# brick_i2c_ktemp.net
KiCad netlist of a schematic drawn in EAGLE
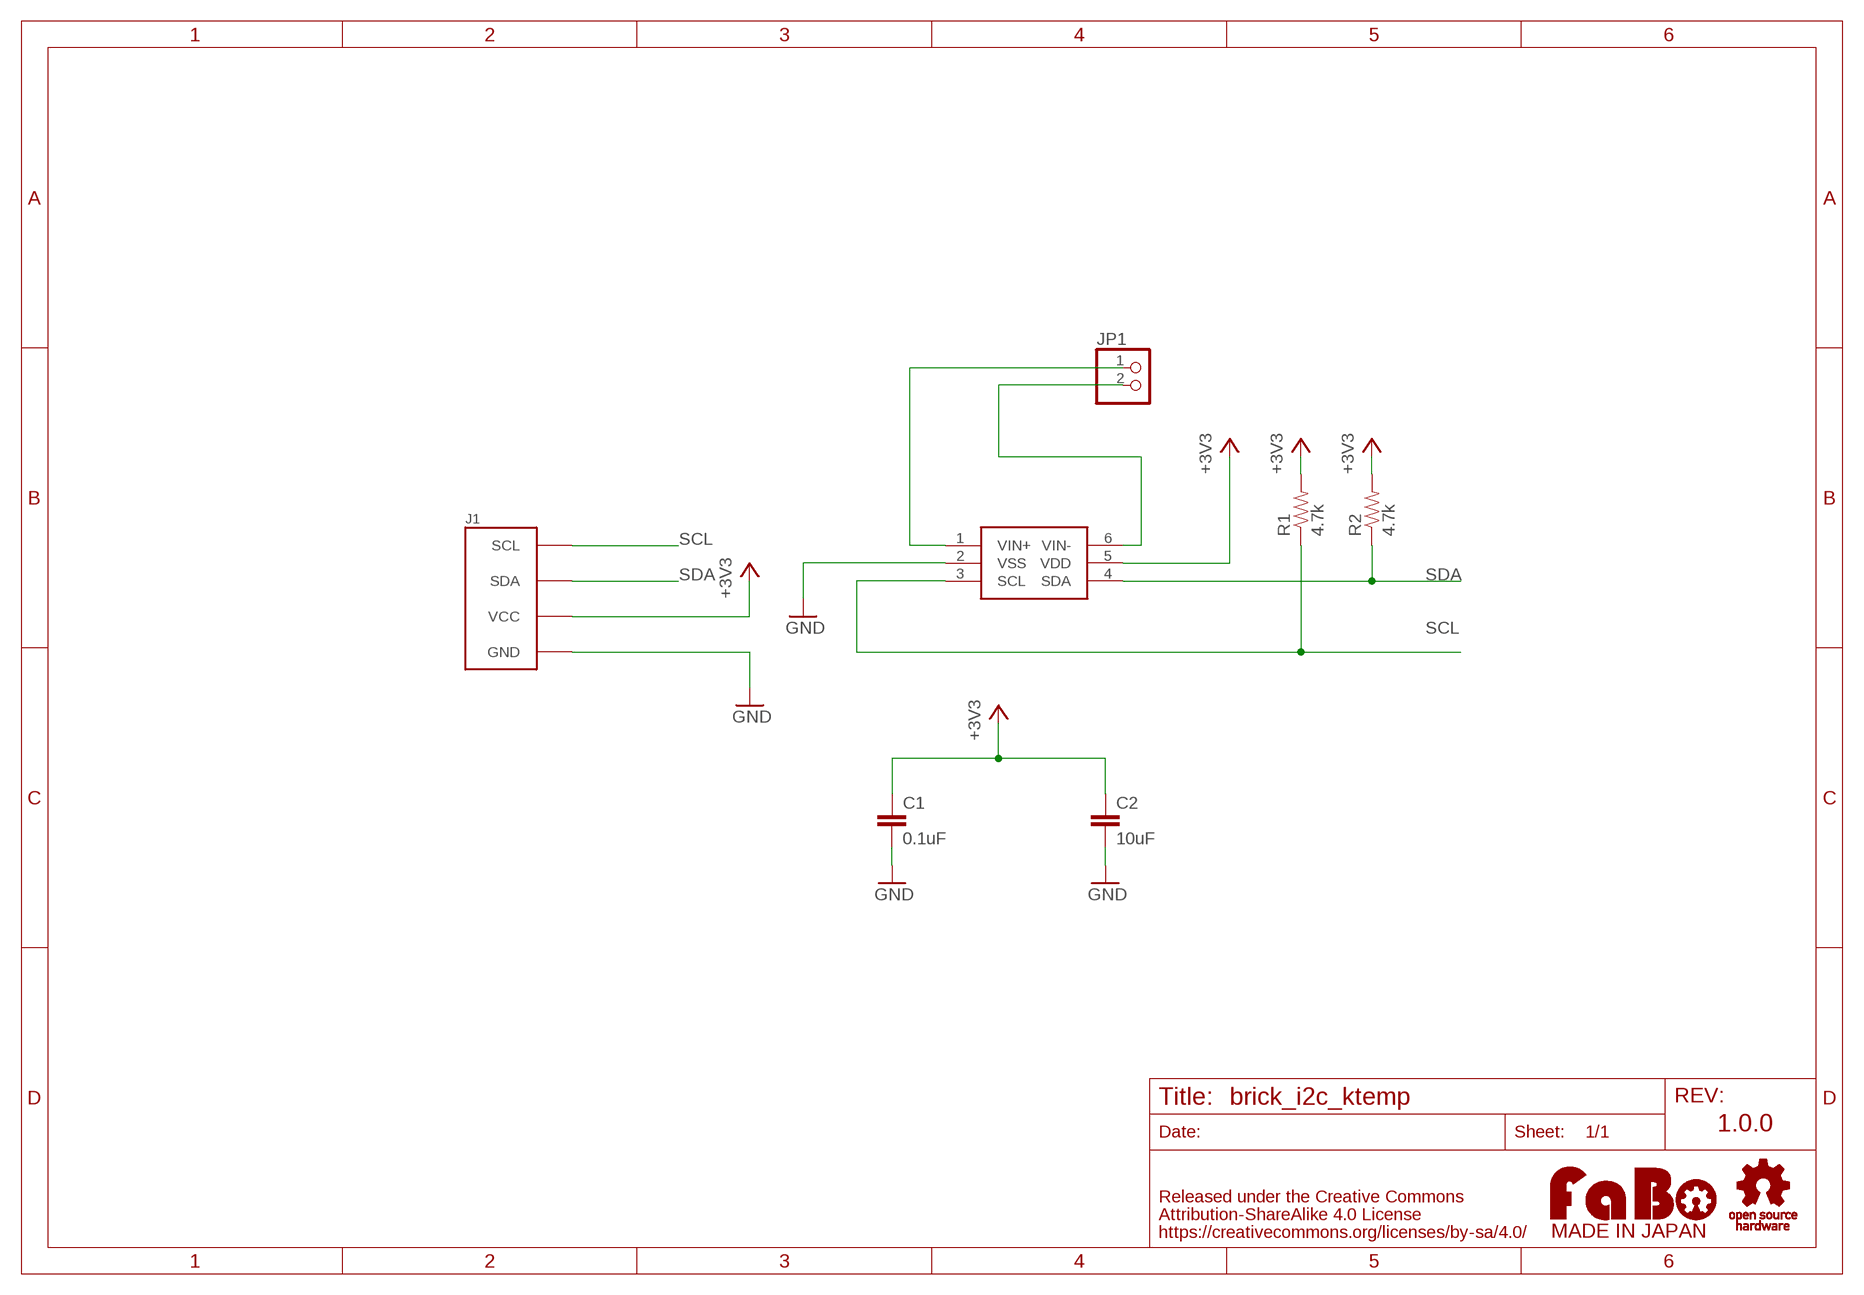
[diagram p0: schematic, sheet 1]

(export (version "E")
  (design (tool "Eeschema 10.0.6"))
  (components
    (comp (ref "C1")
      (value "0.1uF")
      (footprint "eagle-import:EIA0603")
      (libsource (lib "eagle-import") (part "CAP-EIA0603"))
    )
    (comp (ref "C2")
      (value "10uF")
      (footprint "eagle-import:EIA0603")
      (libsource (lib "eagle-import") (part "CAP-EIA0603"))
    )
    (comp (ref "J1")
      (value "BRICK_I2C")
      (footprint "eagle-import:BRICK_I2C")
      (libsource (lib "eagle-import") (part "BRICK_I2C"))
    )
    (comp (ref "JP1")
      (value "PINHD-1X2")
      (footprint "eagle-import:1X02")
      (libsource (lib "eagle-import") (part "PINHD-1X2"))
    )
    (comp (ref "R1")
      (value "4.7k")
      (footprint "eagle-import:EIA0603")
      (libsource (lib "eagle-import") (part "RES-EIA0603"))
    )
    (comp (ref "R2")
      (value "4.7k")
      (footprint "eagle-import:EIA0603")
      (libsource (lib "eagle-import") (part "RES-EIA0603"))
    )
    (comp (ref "U$2")
      (value "MICROCHIP-MCP3421")
      (footprint "eagle-import:MICROCHIP-MCP3421")
      (libsource (lib "eagle-import") (part "MICROCHIP-MCP3421"))
    )
    (comp (ref "U$3")
      (value "LOGO_OSHW_T-M")
      (footprint "eagle-import:LOGO_OSHW_T_M")
      (libsource (lib "eagle-import") (part "LOGO_OSHW_T-M"))
    )
    (comp (ref "U$4")
      (value "LOGO_FABO-M")
      (footprint "eagle-import:LOGO_FABO_M")
      (libsource (lib "eagle-import") (part "LOGO_FABO-M"))
    )
  )
  (nets
    (net (code "1") (name "+3V3") (class "Default")
      (node (ref "C1") (pin "1") (pinfunction "1_1") (pintype "passive"))
      (node (ref "C2") (pin "1") (pinfunction "1_1") (pintype "passive"))
      (node (ref "J1") (pin "VCC") (pinfunction "VCC_VCC") (pintype "bidirectional"))
      (node (ref "R1") (pin "2") (pinfunction "2_2") (pintype "passive"))
      (node (ref "R2") (pin "2") (pinfunction "2_2") (pintype "passive"))
      (node (ref "U$2") (pin "5") (pinfunction "VDD_5") (pintype "bidirectional"))
    )
    (net (code "2") (name "/SCL") (class "Default")
      (node (ref "J1") (pin "SCL") (pinfunction "SCL_SCL") (pintype "bidirectional"))
      (node (ref "R1") (pin "1") (pinfunction "1_1") (pintype "passive"))
      (node (ref "U$2") (pin "3") (pinfunction "SCL_3") (pintype "bidirectional"))
    )
    (net (code "3") (name "/SDA") (class "Default")
      (node (ref "J1") (pin "SDA") (pinfunction "SDA_SDA") (pintype "bidirectional"))
      (node (ref "R2") (pin "1") (pinfunction "1_1") (pintype "passive"))
      (node (ref "U$2") (pin "4") (pinfunction "SDA_4") (pintype "bidirectional"))
    )
    (net (code "4") (name "GND") (class "Default")
      (node (ref "C1") (pin "2") (pinfunction "2_2") (pintype "passive"))
      (node (ref "C2") (pin "2") (pinfunction "2_2") (pintype "passive"))
      (node (ref "J1") (pin "GND") (pinfunction "GND_GND") (pintype "bidirectional"))
      (node (ref "U$2") (pin "2") (pinfunction "VSS_2") (pintype "bidirectional"))
    )
    (net (code "5") (name "Net-(U$2-VIN+)") (class "Default")
      (node (ref "JP1") (pin "1") (pinfunction "1_1") (pintype "passive"))
      (node (ref "U$2") (pin "1") (pinfunction "VIN+_1") (pintype "bidirectional"))
    )
    (net (code "6") (name "Net-(U$2-VIN-)") (class "Default")
      (node (ref "JP1") (pin "2") (pinfunction "2_2") (pintype "passive"))
      (node (ref "U$2") (pin "6") (pinfunction "VIN-_6") (pintype "bidirectional"))
    )
  )
)
